# node.net
KiCad netlist of a schematic drawn in EAGLE
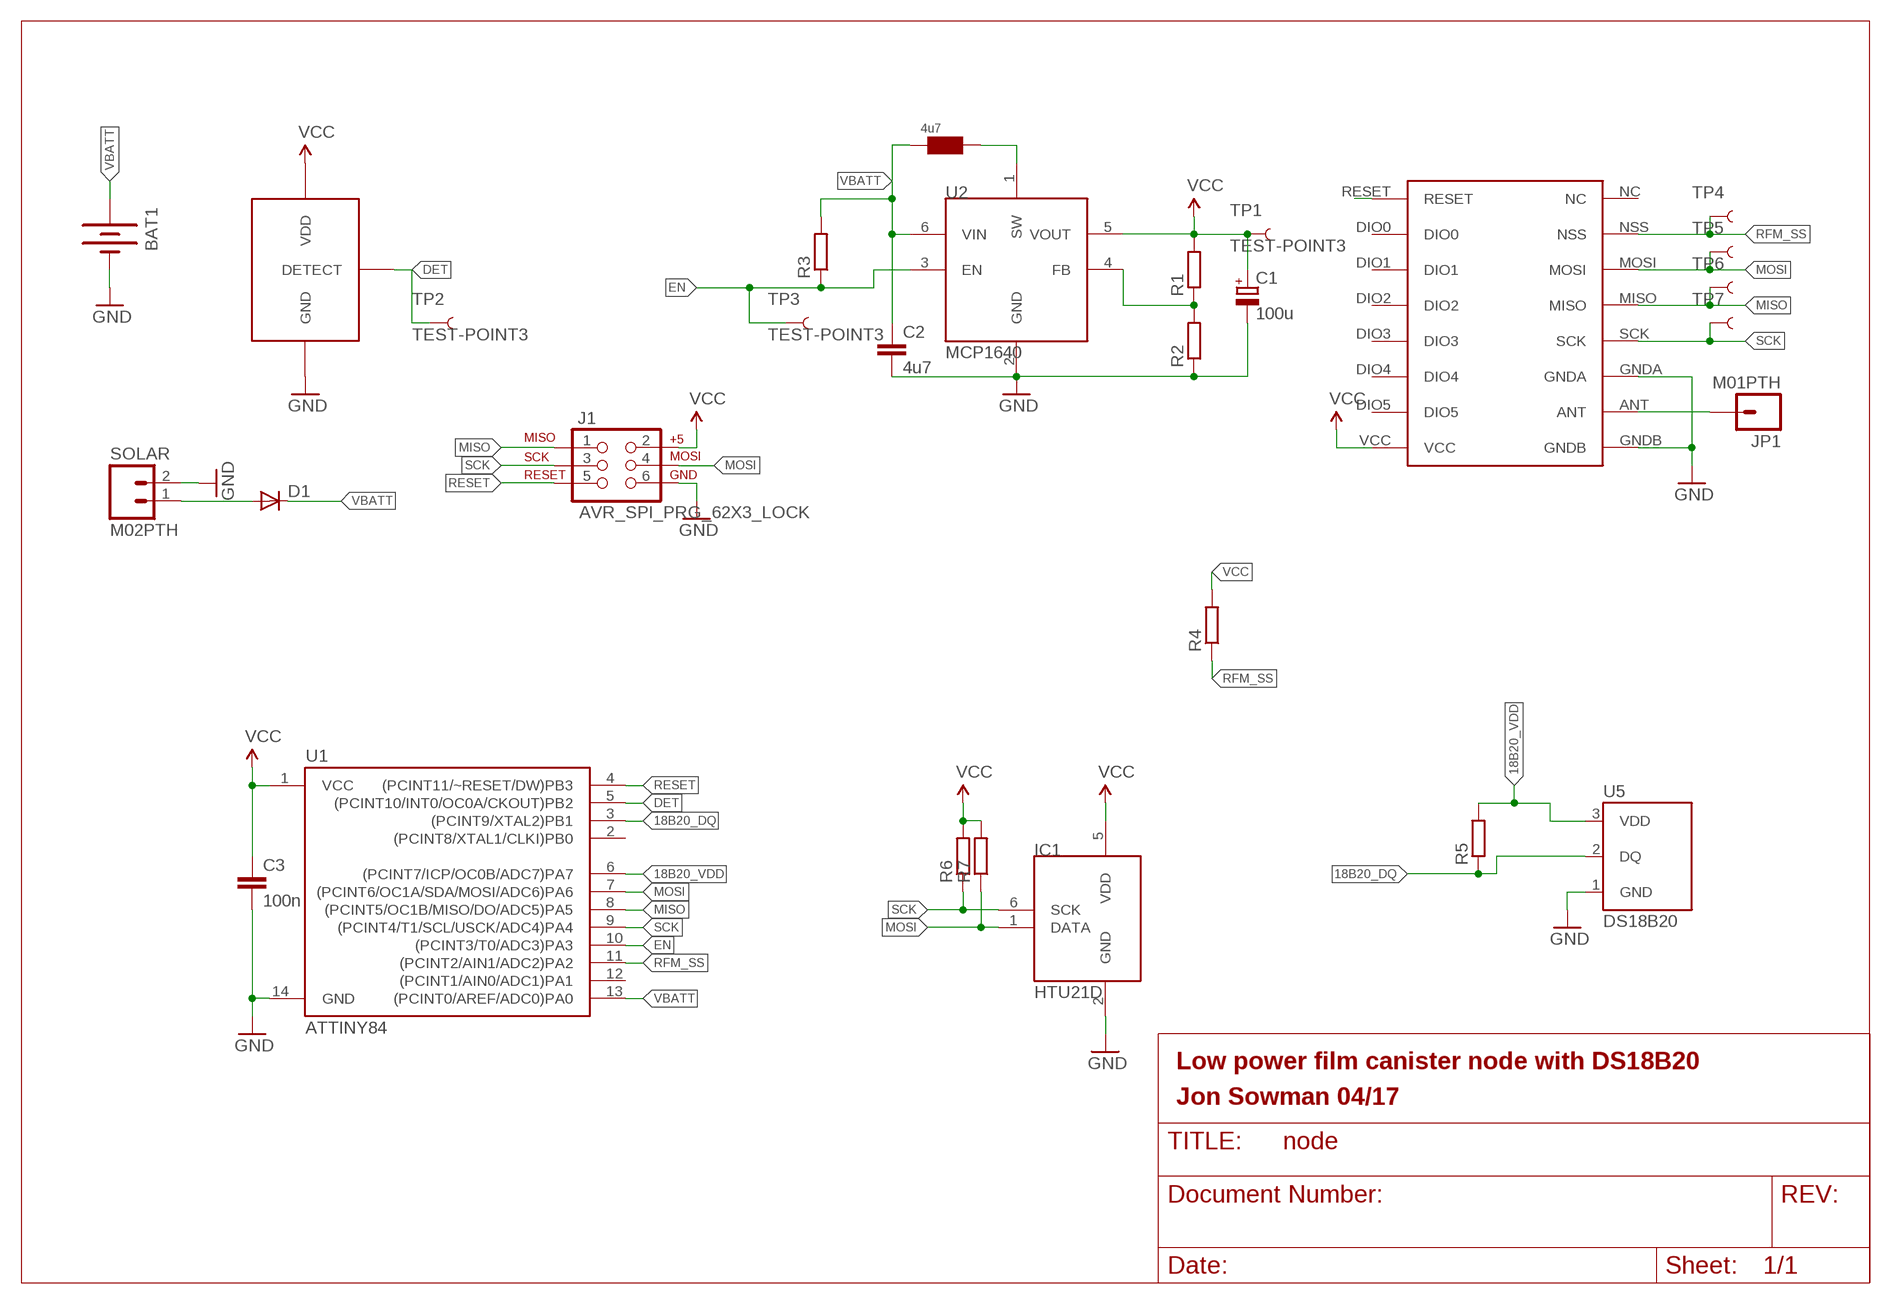
[diagram p0: schematic, sheet 1]

(export (version "E")
  (design (tool "Eeschema 10.0.6"))
  (components
    (comp (ref "BAT1")
      (value "BATTERYAAA")
      (footprint "eagle-import:BATTERY-AAA")
      (libsource (lib "eagle-import") (part "BATTERYAAA"))
    )
    (comp (ref "C1")
      (value "100u")
      (footprint "eagle-import:SANYO-OSCON_SMD_C6")
      (libsource (lib "eagle-import") (part "CPOL-EUSANYO_SMD_C6"))
    )
    (comp (ref "C2")
      (value "4u7")
      (footprint "eagle-import:C0603")
      (libsource (lib "eagle-import") (part "C-EUC0603"))
    )
    (comp (ref "C3")
      (value "100n")
      (footprint "eagle-import:C0603")
      (libsource (lib "eagle-import") (part "C-EUC0603"))
    )
    (comp (ref "D1")
      (value "DIODE-SOD123")
      (footprint "eagle-import:SOD123")
      (libsource (lib "eagle-import") (part "DIODE-SOD123"))
    )
    (comp (ref "DF")
      (value "4u7")
      (footprint "eagle-import:BOURNS_SRN5040_L")
      (libsource (lib "eagle-import") (part "BOURNS_SRN5040"))
    )
    (comp (ref "IC1")
      (value "HTU21D")
      (footprint "eagle-import:DFN6-L")
      (libsource (lib "eagle-import") (part "HTU21D"))
    )
    (comp (ref "J1")
      (value "AVR_SPI_PRG_62X3_LOCK")
      (footprint "eagle-import:2X3_LOCK")
      (libsource (lib "eagle-import") (part "AVR_SPI_PRG_62X3_LOCK"))
    )
    (comp (ref "JP1")
      (value "M01PTH")
      (footprint "eagle-import:1X01")
      (libsource (lib "eagle-import") (part "M01PTH"))
    )
    (comp (ref "R1")
      (value "R-EU_R0603")
      (footprint "eagle-import:R0603")
      (libsource (lib "eagle-import") (part "R-EU_R0603"))
    )
    (comp (ref "R2")
      (value "R-EU_R0603")
      (footprint "eagle-import:R0603")
      (libsource (lib "eagle-import") (part "R-EU_R0603"))
    )
    (comp (ref "R3")
      (value "R-EU_R0603")
      (footprint "eagle-import:R0603")
      (libsource (lib "eagle-import") (part "R-EU_R0603"))
    )
    (comp (ref "R4")
      (value "R-EU_R0603")
      (footprint "eagle-import:R0603")
      (libsource (lib "eagle-import") (part "R-EU_R0603"))
    )
    (comp (ref "R5")
      (value "R-EU_R0603")
      (footprint "eagle-import:R0603")
      (libsource (lib "eagle-import") (part "R-EU_R0603"))
    )
    (comp (ref "R6")
      (value "R-EU_R0603")
      (footprint "eagle-import:R0603")
      (libsource (lib "eagle-import") (part "R-EU_R0603"))
    )
    (comp (ref "R7")
      (value "R-EU_R0603")
      (footprint "eagle-import:R0603")
      (libsource (lib "eagle-import") (part "R-EU_R0603"))
    )
    (comp (ref "SOLAR")
      (value "M02PTH")
      (footprint "eagle-import:1X02")
      (libsource (lib "eagle-import") (part "M02PTH"))
    )
    (comp (ref "TP1")
      (value "TEST-POINT3")
      (footprint "eagle-import:PAD.03X.03")
      (libsource (lib "eagle-import") (part "TEST-POINT3"))
    )
    (comp (ref "TP2")
      (value "TEST-POINT3")
      (footprint "eagle-import:PAD.03X.03")
      (libsource (lib "eagle-import") (part "TEST-POINT3"))
    )
    (comp (ref "TP3")
      (value "TEST-POINT3")
      (footprint "eagle-import:PAD.03X.03")
      (libsource (lib "eagle-import") (part "TEST-POINT3"))
    )
    (comp (ref "TP4")
      (value "TEST-POINT3")
      (footprint "eagle-import:PAD.03X.03")
      (libsource (lib "eagle-import") (part "TEST-POINT3"))
    )
    (comp (ref "TP5")
      (value "TEST-POINT3")
      (footprint "eagle-import:PAD.03X.03")
      (libsource (lib "eagle-import") (part "TEST-POINT3"))
    )
    (comp (ref "TP6")
      (value "TEST-POINT3")
      (footprint "eagle-import:PAD.03X.03")
      (libsource (lib "eagle-import") (part "TEST-POINT3"))
    )
    (comp (ref "TP7")
      (value "TEST-POINT3")
      (footprint "eagle-import:PAD.03X.03")
      (libsource (lib "eagle-import") (part "TEST-POINT3"))
    )
    (comp (ref "U$4")
      (value "RFM69HW")
      (footprint "eagle-import:RFM")
      (libsource (lib "eagle-import") (part "RFM69HW"))
    )
    (comp (ref "U1")
      (value "ATTINY84")
      (footprint "eagle-import:SO14")
      (libsource (lib "eagle-import") (part "ATTINY84"))
    )
    (comp (ref "U2")
      (value "MCP1640")
      (footprint "eagle-import:SOT23-6")
      (libsource (lib "eagle-import") (part "MCP1640"))
    )
    (comp (ref "U3")
      (value "BU49X_VDET_SOT235")
      (footprint "eagle-import:SOT23-5L")
      (libsource (lib "eagle-import") (part "BU49X_VDET_SOT235"))
    )
    (comp (ref "U5")
      (value "DS18B20")
      (footprint "eagle-import:TO-92-AMMO")
      (libsource (lib "eagle-import") (part "DS18B20"))
    )
  )
  (nets
    (net (code "1") (name "18B20_DQ") (class "Default")
      (node (ref "R5") (pin "1") (pinfunction "1_1") (pintype "passive"))
      (node (ref "U1") (pin "3") (pinfunction "(PCINT9/XTAL2)PB1_3") (pintype "bidirectional"))
      (node (ref "U5") (pin "2") (pinfunction "DQ_2") (pintype "bidirectional"))
    )
    (net (code "2") (name "18B20_VDD") (class "Default")
      (node (ref "R5") (pin "2") (pinfunction "2_2") (pintype "passive"))
      (node (ref "U1") (pin "6") (pinfunction "(PCINT7/ICP/OC0B/ADC7)PA7_6") (pintype "bidirectional"))
      (node (ref "U5") (pin "3") (pinfunction "VDD_3") (pintype "power_in"))
    )
    (net (code "3") (name "DET") (class "Default")
      (node (ref "TP2") (pin "P$1") (pinfunction "1_P$1") (pintype "bidirectional"))
      (node (ref "U1") (pin "5") (pinfunction "(PCINT10/INT0/OC0A/CKOUT)PB2_5") (pintype "bidirectional"))
      (node (ref "U3") (pin "1") (pinfunction "DETECT_1") (pintype "bidirectional"))
    )
    (net (code "4") (name "EN") (class "Default")
      (node (ref "R3") (pin "1") (pinfunction "1_1") (pintype "passive"))
      (node (ref "TP3") (pin "P$1") (pinfunction "1_P$1") (pintype "bidirectional"))
      (node (ref "U1") (pin "10") (pinfunction "(PCINT3/T0/ADC3)PA3_10") (pintype "bidirectional"))
      (node (ref "U2") (pin "3") (pinfunction "EN_3") (pintype "input"))
    )
    (net (code "5") (name "GND") (class "Default")
      (node (ref "BAT1") (pin "GND@1") (pinfunction "-_GND@1") (pintype "power_in"))
      (node (ref "C1") (pin "-") (pinfunction "-_-") (pintype "passive"))
      (node (ref "C2") (pin "2") (pinfunction "2_2") (pintype "passive"))
      (node (ref "C3") (pin "2") (pinfunction "2_2") (pintype "passive"))
      (node (ref "IC1") (pin "2") (pinfunction "GND_2") (pintype "power_in"))
      (node (ref "J1") (pin "6") (pinfunction "6_6") (pintype "passive"))
      (node (ref "R2") (pin "1") (pinfunction "1_1") (pintype "passive"))
      (node (ref "SOLAR") (pin "2") (pinfunction "2_2") (pintype "passive"))
      (node (ref "U$4") (pin "GNDA") (pinfunction "GNDA_GNDA") (pintype "bidirectional"))
      (node (ref "U$4") (pin "GNDB") (pinfunction "GNDB_GNDB") (pintype "bidirectional"))
      (node (ref "U1") (pin "14") (pinfunction "GND_14") (pintype "bidirectional"))
      (node (ref "U2") (pin "2") (pinfunction "GND_2") (pintype "power_in"))
      (node (ref "U3") (pin "3") (pinfunction "GND_3") (pintype "bidirectional"))
      (node (ref "U5") (pin "1") (pinfunction "GND_1") (pintype "power_in"))
    )
    (net (code "6") (name "MISO") (class "Default")
      (node (ref "J1") (pin "1") (pinfunction "1_1") (pintype "passive"))
      (node (ref "TP6") (pin "P$1") (pinfunction "1_P$1") (pintype "bidirectional"))
      (node (ref "U$4") (pin "MISO") (pinfunction "MISO_MISO") (pintype "bidirectional"))
      (node (ref "U1") (pin "8") (pinfunction "(PCINT5/OC1B/MISO/DO/ADC5)PA5_8") (pintype "bidirectional"))
    )
    (net (code "7") (name "MOSI") (class "Default")
      (node (ref "IC1") (pin "1") (pinfunction "DATA_1") (pintype "bidirectional"))
      (node (ref "J1") (pin "4") (pinfunction "4_4") (pintype "passive"))
      (node (ref "R7") (pin "1") (pinfunction "1_1") (pintype "passive"))
      (node (ref "TP5") (pin "P$1") (pinfunction "1_P$1") (pintype "bidirectional"))
      (node (ref "U$4") (pin "MOSI") (pinfunction "MOSI_MOSI") (pintype "bidirectional"))
      (node (ref "U1") (pin "7") (pinfunction "(PCINT6/OC1A/SDA/MOSI/ADC6)PA6_7") (pintype "bidirectional"))
    )
    (net (code "8") (name "Net-(D1-PadA)") (class "Default")
      (node (ref "D1") (pin "A") (pinfunction "A_A") (pintype "passive"))
      (node (ref "SOLAR") (pin "1") (pinfunction "1_1") (pintype "passive"))
    )
    (net (code "9") (name "Net-(JP1-Pad1)") (class "Default")
      (node (ref "JP1") (pin "1") (pinfunction "1_1") (pintype "passive"))
      (node (ref "U$4") (pin "ANT") (pinfunction "ANT_ANT") (pintype "bidirectional"))
    )
    (net (code "10") (name "Net-(U2-FB)") (class "Default")
      (node (ref "R1") (pin "1") (pinfunction "1_1") (pintype "passive"))
      (node (ref "R2") (pin "2") (pinfunction "2_2") (pintype "passive"))
      (node (ref "U2") (pin "4") (pinfunction "FB_4") (pintype "input"))
    )
    (net (code "11") (name "Net-(U2-SW)") (class "Default")
      (node (ref "DF") (pin "P$2") (pinfunction "P$2_P$2") (pintype "bidirectional"))
      (node (ref "U2") (pin "1") (pinfunction "SW_1") (pintype "input"))
    )
    (net (code "12") (name "RESET") (class "Default")
      (node (ref "J1") (pin "5") (pinfunction "5_5") (pintype "passive"))
      (node (ref "U1") (pin "4") (pinfunction "(PCINT11/~{RESET/DW})PB3_4") (pintype "bidirectional"))
    )
    (net (code "13") (name "RFM_SS") (class "Default")
      (node (ref "R4") (pin "1") (pinfunction "1_1") (pintype "passive"))
      (node (ref "TP4") (pin "P$1") (pinfunction "1_P$1") (pintype "bidirectional"))
      (node (ref "U$4") (pin "NSS") (pinfunction "NSS_NSS") (pintype "bidirectional"))
      (node (ref "U1") (pin "11") (pinfunction "(PCINT2/AIN1/ADC2)PA2_11") (pintype "bidirectional"))
    )
    (net (code "14") (name "SCK") (class "Default")
      (node (ref "IC1") (pin "6") (pinfunction "SCK_6") (pintype "input"))
      (node (ref "J1") (pin "3") (pinfunction "3_3") (pintype "passive"))
      (node (ref "R6") (pin "1") (pinfunction "1_1") (pintype "passive"))
      (node (ref "TP7") (pin "P$1") (pinfunction "1_P$1") (pintype "bidirectional"))
      (node (ref "U$4") (pin "SCK") (pinfunction "SCK_SCK") (pintype "bidirectional"))
      (node (ref "U1") (pin "9") (pinfunction "(PCINT4/T1/SCL/USCK/ADC4)PA4_9") (pintype "bidirectional"))
    )
    (net (code "15") (name "VBATT") (class "Default")
      (node (ref "BAT1") (pin "PWR@1") (pinfunction "+_PWR@1") (pintype "power_in"))
      (node (ref "C2") (pin "1") (pinfunction "1_1") (pintype "passive"))
      (node (ref "D1") (pin "C") (pinfunction "C_C") (pintype "passive"))
      (node (ref "DF") (pin "P$1") (pinfunction "P$1_P$1") (pintype "bidirectional"))
      (node (ref "R3") (pin "2") (pinfunction "2_2") (pintype "passive"))
      (node (ref "U1") (pin "13") (pinfunction "(PCINT0/AREF/ADC0)PA0_13") (pintype "bidirectional"))
      (node (ref "U2") (pin "6") (pinfunction "VIN_6") (pintype "power_in"))
    )
    (net (code "16") (name "VCC") (class "Default")
      (node (ref "C1") (pin "+") (pinfunction "+_+") (pintype "passive"))
      (node (ref "C3") (pin "1") (pinfunction "1_1") (pintype "passive"))
      (node (ref "IC1") (pin "5") (pinfunction "VDD_5") (pintype "power_in"))
      (node (ref "J1") (pin "2") (pinfunction "2_2") (pintype "passive"))
      (node (ref "R1") (pin "2") (pinfunction "2_2") (pintype "passive"))
      (node (ref "R4") (pin "2") (pinfunction "2_2") (pintype "passive"))
      (node (ref "R6") (pin "2") (pinfunction "2_2") (pintype "passive"))
      (node (ref "R7") (pin "2") (pinfunction "2_2") (pintype "passive"))
      (node (ref "TP1") (pin "P$1") (pinfunction "1_P$1") (pintype "bidirectional"))
      (node (ref "U$4") (pin "VCC") (pinfunction "VCC_VCC") (pintype "bidirectional"))
      (node (ref "U1") (pin "1") (pinfunction "VCC_1") (pintype "bidirectional"))
      (node (ref "U2") (pin "5") (pinfunction "VOUT_5") (pintype "output"))
      (node (ref "U3") (pin "2") (pinfunction "VDD_2") (pintype "bidirectional"))
    )
    (net (code "17") (name "unconnected-(U$4-PadDIO0)") (class "Default")
      (node (ref "U$4") (pin "DIO0") (pinfunction "DIO0_DIO0") (pintype "bidirectional"))
    )
    (net (code "18") (name "unconnected-(U$4-PadDIO1)") (class "Default")
      (node (ref "U$4") (pin "DIO1") (pinfunction "DIO1_DIO1") (pintype "bidirectional"))
    )
    (net (code "19") (name "unconnected-(U$4-PadDIO2)") (class "Default")
      (node (ref "U$4") (pin "DIO2") (pinfunction "DIO2_DIO2") (pintype "bidirectional"))
    )
    (net (code "20") (name "unconnected-(U$4-PadDIO3)") (class "Default")
      (node (ref "U$4") (pin "DIO3") (pinfunction "DIO3_DIO3") (pintype "bidirectional"))
    )
    (net (code "21") (name "unconnected-(U$4-PadDIO4)") (class "Default")
      (node (ref "U$4") (pin "DIO4") (pinfunction "DIO4_DIO4") (pintype "bidirectional"))
    )
    (net (code "22") (name "unconnected-(U$4-PadDIO5)") (class "Default")
      (node (ref "U$4") (pin "DIO5") (pinfunction "DIO5_DIO5") (pintype "bidirectional"))
    )
    (net (code "23") (name "unconnected-(U$4-PadNC)") (class "Default")
      (node (ref "U$4") (pin "NC") (pinfunction "NC_NC") (pintype "bidirectional"))
    )
    (net (code "24") (name "unconnected-(U$4-PadRESET)") (class "Default")
      (node (ref "U$4") (pin "RESET") (pinfunction "RESET_RESET") (pintype "bidirectional"))
    )
    (net (code "25") (name "unconnected-(U1-(PCINT1{slash}AIN0{slash}ADC1)PA1-Pad12)") (class "Default")
      (node (ref "U1") (pin "12") (pinfunction "(PCINT1/AIN0/ADC1)PA1_12") (pintype "bidirectional"))
    )
    (net (code "26") (name "unconnected-(U1-(PCINT8{slash}XTAL1{slash}CLKI)PB0-Pad2)") (class "Default")
      (node (ref "U1") (pin "2") (pinfunction "(PCINT8/XTAL1/CLKI)PB0_2") (pintype "bidirectional"))
    )
  )
)
